# Top.net
KiCad netlist of a schematic drawn in Altium Designer
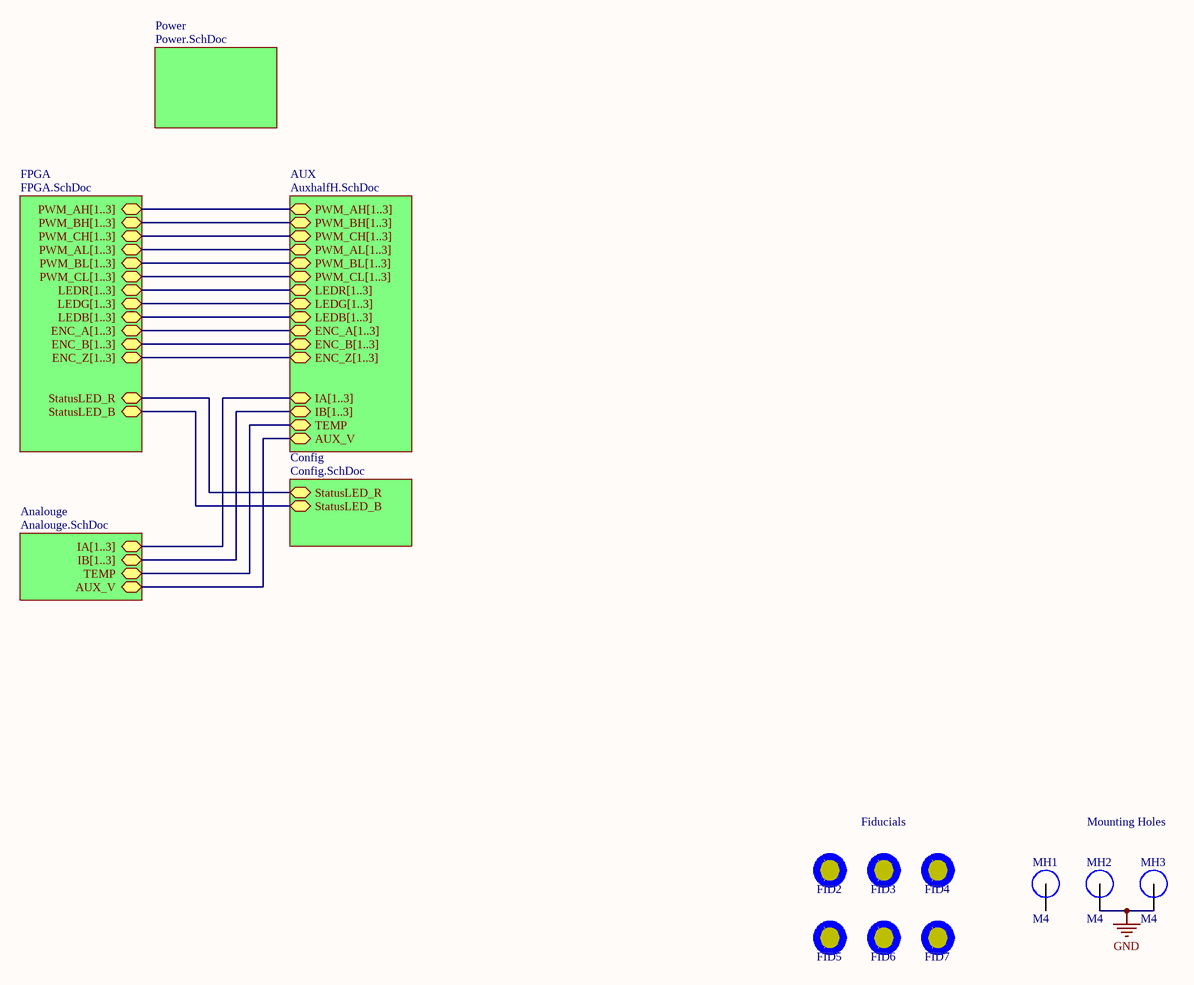
[diagram p0: Top.SchDoc]

(export (version "E")
  (design (tool "Eeschema 10.0.6"))
  (components
    (comp (ref "FID2")
      (value "FIDUCIAL")
      (footprint "FIDUCIAL")
      (description "1mm Fiducial with 2mm soldermask, 3mm keepout")
      (libsource (lib "CustomComponents") (part "FIDUCIAL"))
    )
    (comp (ref "FID3")
      (value "FIDUCIAL")
      (footprint "FIDUCIAL")
      (description "1mm Fiducial with 2mm soldermask, 3mm keepout")
      (libsource (lib "CustomComponents") (part "FIDUCIAL"))
    )
    (comp (ref "FID4")
      (value "FIDUCIAL")
      (footprint "FIDUCIAL")
      (description "1mm Fiducial with 2mm soldermask, 3mm keepout")
      (libsource (lib "CustomComponents") (part "FIDUCIAL"))
    )
    (comp (ref "FID5")
      (value "FIDUCIAL")
      (footprint "FIDUCIAL")
      (description "1mm Fiducial with 2mm soldermask, 3mm keepout")
      (libsource (lib "CustomComponents") (part "FIDUCIAL"))
    )
    (comp (ref "FID6")
      (value "FIDUCIAL")
      (footprint "FIDUCIAL")
      (description "1mm Fiducial with 2mm soldermask, 3mm keepout")
      (libsource (lib "CustomComponents") (part "FIDUCIAL"))
    )
    (comp (ref "FID7")
      (value "FIDUCIAL")
      (footprint "FIDUCIAL")
      (description "1mm Fiducial with 2mm soldermask, 3mm keepout")
      (libsource (lib "CustomComponents") (part "FIDUCIAL"))
    )
    (comp (ref "MH1")
      (value "M4")
      (footprint "MH_M4")
      (description "M4 Mounting Hole")
      (libsource (lib "CustomComponents") (part "MH_M4"))
    )
    (comp (ref "MH2")
      (value "M4")
      (footprint "MH_M4")
      (description "M4 Mounting Hole")
      (libsource (lib "CustomComponents") (part "MH_M4"))
    )
    (comp (ref "MH3")
      (value "M4")
      (footprint "MH_M4")
      (description "M4 Mounting Hole")
      (libsource (lib "CustomComponents") (part "MH_M4"))
    )
  )
  (nets
    (net (code "19") (name "GND") (class "Default")
      (node (ref "MH2") (pin "1") (pinfunction "1_1") (pintype "passive"))
      (node (ref "MH3") (pin "1") (pinfunction "1_1") (pintype "passive"))
    )
    (net (code "20") (name "unconnected-(MH1-Pad1)") (class "Default")
      (node (ref "MH1") (pin "1") (pinfunction "1_1") (pintype "passive"))
    )
  )
)
